# s2.net
KiCad netlist of a schematic drawn in EAGLE
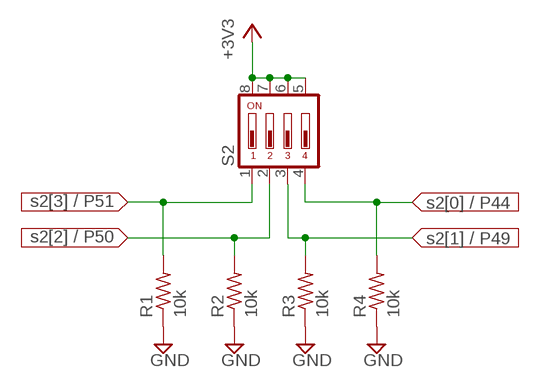
[diagram p0: schematic, sheet 1]

(export (version "E")
  (design (tool "Eeschema 10.0.6"))
  (components
    (comp (ref "R1")
      (value "10k")
      (footprint "eagle-import:0207_10")
      (libsource (lib "eagle-import") (part "R-US_0207/10"))
    )
    (comp (ref "R2")
      (value "10k")
      (footprint "eagle-import:0207_10")
      (libsource (lib "eagle-import") (part "R-US_0207/10"))
    )
    (comp (ref "R3")
      (value "10k")
      (footprint "eagle-import:0207_10")
      (libsource (lib "eagle-import") (part "R-US_0207/10"))
    )
    (comp (ref "R4")
      (value "10k")
      (footprint "eagle-import:0207_10")
      (libsource (lib "eagle-import") (part "R-US_0207/10"))
    )
    (comp (ref "S2")
      (value "DIP04YL")
      (footprint "eagle-import:DIP04YL")
      (libsource (lib "eagle-import") (part "DIP04YL"))
    )
  )
  (nets
    (net (code "1") (name "+3V3") (class "Default")
      (node (ref "S2") (pin "5") (pinfunction "5_5") (pintype "passive"))
      (node (ref "S2") (pin "6") (pinfunction "6_6") (pintype "passive"))
      (node (ref "S2") (pin "7") (pinfunction "7_7") (pintype "passive"))
      (node (ref "S2") (pin "8") (pinfunction "8_8") (pintype "passive"))
    )
    (net (code "2") (name "GND") (class "Default")
      (node (ref "R1") (pin "1") (pinfunction "1_1") (pintype "passive"))
      (node (ref "R2") (pin "1") (pinfunction "1_1") (pintype "passive"))
      (node (ref "R3") (pin "1") (pinfunction "1_1") (pintype "passive"))
      (node (ref "R4") (pin "1") (pinfunction "1_1") (pintype "passive"))
    )
    (net (code "3") (name "Net-(R1-Pad2)") (class "Default")
      (node (ref "R1") (pin "2") (pinfunction "2_2") (pintype "passive"))
      (node (ref "S2") (pin "1") (pinfunction "1_1") (pintype "passive"))
    )
    (net (code "4") (name "Net-(R2-Pad2)") (class "Default")
      (node (ref "R2") (pin "2") (pinfunction "2_2") (pintype "passive"))
      (node (ref "S2") (pin "2") (pinfunction "2_2") (pintype "passive"))
    )
    (net (code "5") (name "Net-(R3-Pad2)") (class "Default")
      (node (ref "R3") (pin "2") (pinfunction "2_2") (pintype "passive"))
      (node (ref "S2") (pin "3") (pinfunction "3_3") (pintype "passive"))
    )
    (net (code "6") (name "Net-(R4-Pad2)") (class "Default")
      (node (ref "R4") (pin "2") (pinfunction "2_2") (pintype "passive"))
      (node (ref "S2") (pin "4") (pinfunction "4_4") (pintype "passive"))
    )
  )
)
